# slush_cap_board_rev_e.net
KiCad netlist of a schematic drawn in EAGLE
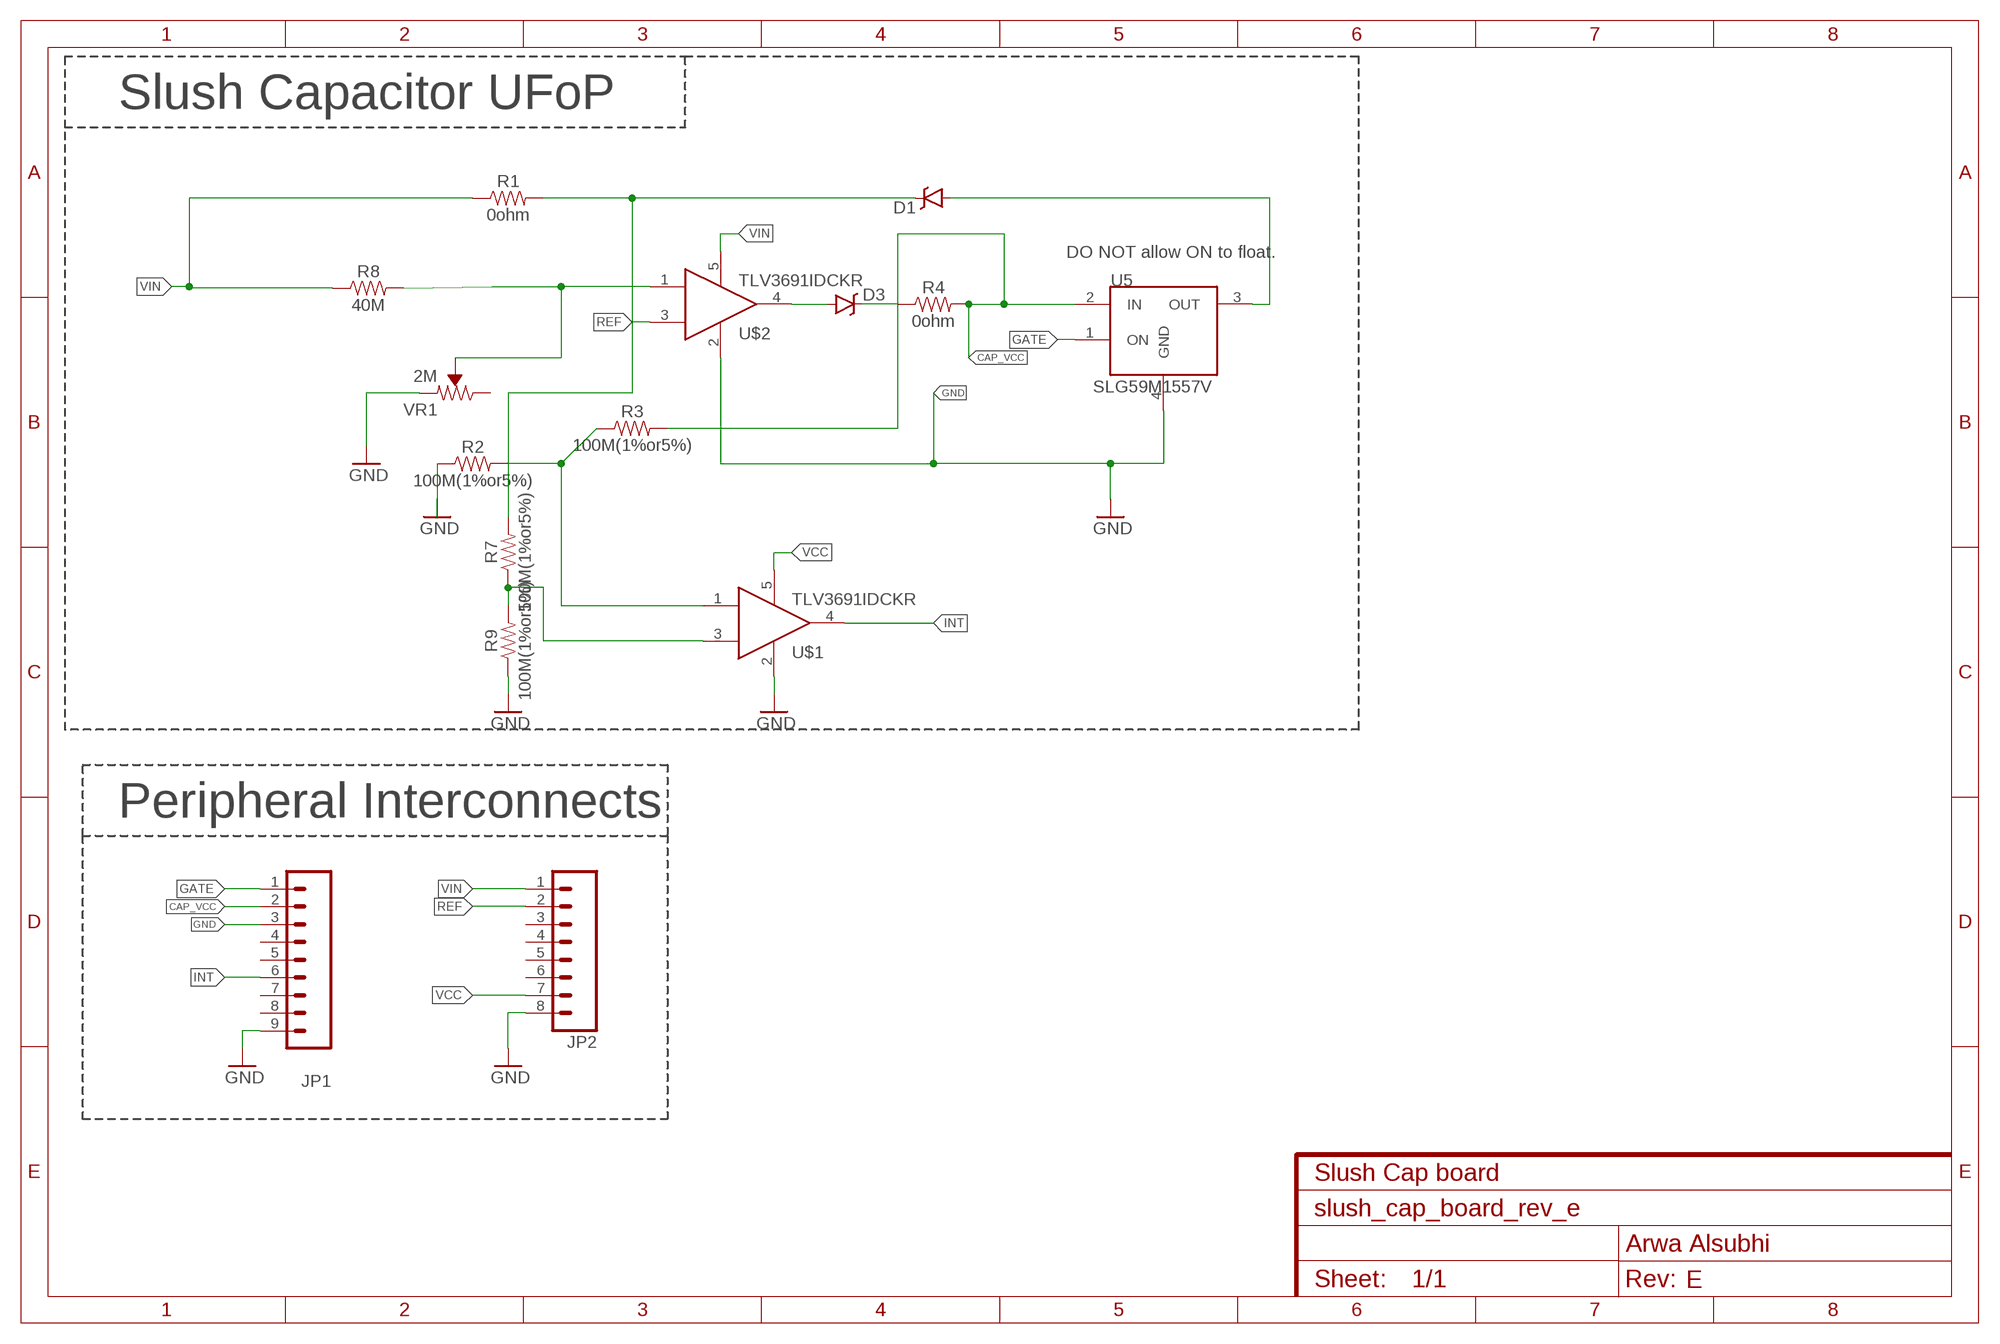
[diagram p0: schematic, sheet 1]

(export (version "E")
  (design (tool "Eeschema 10.0.6"))
  (components
    (comp (ref "D1")
      (value "RB751")
      (footprint "eagle-import:SOD-523")
      (fields (field (name "MPN") "BAS40-02V-V-G-08"))
      (libsource (lib "eagle-import") (part "DIODE-SCHOTTKY-RB751"))
    )
    (comp (ref "D3")
      (value "RB751")
      (footprint "eagle-import:SOD-523")
      (fields (field (name "MPN") "BAS40-02V-V-G-08"))
      (libsource (lib "eagle-import") (part "DIODE-SCHOTTKY-RB751"))
    )
    (comp (ref "JP1")
      (value "M091.27MM")
      (footprint "eagle-import:1X09-1.27MM")
      (fields (field (name "MANUFACTURERPARTNUMBER") "GRPB091VWVN-RC ") (field (name "MPN") "GRPB091VWVN-RC"))
      (libsource (lib "eagle-import") (part "M091.27MM"))
    )
    (comp (ref "JP2")
      (value "M081.27MM")
      (footprint "eagle-import:1X08-1.27MM")
      (fields (field (name "MANUFACTURERPARTNUMBER") "GRPB081VWVN-RC "))
      (libsource (lib "eagle-import") (part "M081.27MM"))
    )
    (comp (ref "R1")
      (value "0ohm")
      (footprint "eagle-import:0603")
      (libsource (lib "eagle-import") (part "0603-RESISTOR-0603-1/10W-1%"))
    )
    (comp (ref "R2")
      (value "100M(1%or5%)")
      (footprint "eagle-import:0805")
      (libsource (lib "eagle-import") (part "0.3OHM-0805-1/8W-1%"))
    )
    (comp (ref "R3")
      (value "100M(1%or5%)")
      (footprint "eagle-import:0805")
      (libsource (lib "eagle-import") (part "0.3OHM-0805-1/8W-1%"))
    )
    (comp (ref "R4")
      (value "0ohm")
      (footprint "eagle-import:0603")
      (libsource (lib "eagle-import") (part "0603-RESISTOR-0603-1/10W-1%"))
    )
    (comp (ref "R7")
      (value "100M(1%or5%)")
      (footprint "eagle-import:0805")
      (libsource (lib "eagle-import") (part "0.3OHM-0805-1/8W-1%"))
    )
    (comp (ref "R8")
      (value "40M")
      (footprint "eagle-import:0805")
      (libsource (lib "eagle-import") (part "0.3OHM-0805-1/8W-1%"))
    )
    (comp (ref "R9")
      (value "100M(1%or5%)")
      (footprint "eagle-import:0805")
      (libsource (lib "eagle-import") (part "0.3OHM-0805-1/8W-1%"))
    )
    (comp (ref "U$1")
      (value "TLV3691IDCKR")
      (footprint "eagle-import:SOT353")
      (libsource (lib "eagle-import") (part "TLV3691IDCKR"))
    )
    (comp (ref "U$2")
      (value "TLV3691IDCKR")
      (footprint "eagle-import:SOT353")
      (libsource (lib "eagle-import") (part "TLV3691IDCKR"))
    )
    (comp (ref "U5")
      (value "SLG59M1557V")
      (footprint "eagle-import:4STDFN")
      (fields (field (name "MPN") "SLG59M1557V "))
      (libsource (lib "eagle-import") (part "SLG59M1557V"))
    )
    (comp (ref "VR1")
      (value "2M")
      (footprint "eagle-import:TRIMPOT-SMD-3MM-CLOSED")
      (libsource (lib "eagle-import") (part "TRIMPOT-SMD-3MM-CLOSED-1/8W-20%"))
    )
  )
  (nets
    (net (code "1") (name "CAP_VCC") (class "Default")
      (node (ref "JP1") (pin "2") (pinfunction "2_2") (pintype "passive"))
      (node (ref "R3") (pin "2") (pinfunction "2_2") (pintype "passive"))
      (node (ref "R4") (pin "2") (pinfunction "2_2") (pintype "passive"))
      (node (ref "U5") (pin "2") (pinfunction "IN_2") (pintype "bidirectional"))
    )
    (net (code "2") (name "GATE") (class "Default")
      (node (ref "JP1") (pin "1") (pinfunction "1_1") (pintype "passive"))
      (node (ref "U5") (pin "1") (pinfunction "ON_1") (pintype "bidirectional"))
    )
    (net (code "3") (name "GND") (class "Default")
      (node (ref "JP1") (pin "3") (pinfunction "3_3") (pintype "passive"))
      (node (ref "JP1") (pin "9") (pinfunction "9_9") (pintype "passive"))
      (node (ref "JP2") (pin "8") (pinfunction "8_8") (pintype "passive"))
      (node (ref "R2") (pin "1") (pinfunction "1_1") (pintype "passive"))
      (node (ref "R9") (pin "1") (pinfunction "1_1") (pintype "passive"))
      (node (ref "U$1") (pin "2") (pinfunction "2_2") (pintype "bidirectional"))
      (node (ref "U$2") (pin "2") (pinfunction "2_2") (pintype "bidirectional"))
      (node (ref "U5") (pin "4") (pinfunction "GND_4") (pintype "bidirectional"))
      (node (ref "VR1") (pin "1") (pinfunction "CCW_1") (pintype "passive"))
    )
    (net (code "4") (name "INT") (class "Default")
      (node (ref "JP1") (pin "6") (pinfunction "6_6") (pintype "passive"))
      (node (ref "U$1") (pin "4") (pinfunction "4_4") (pintype "bidirectional"))
    )
    (net (code "5") (name "Net-(D1-PadC)") (class "Default")
      (node (ref "D1") (pin "C") (pinfunction "C_C") (pintype "passive"))
      (node (ref "R1") (pin "2") (pinfunction "2_2") (pintype "passive"))
      (node (ref "R7") (pin "2") (pinfunction "2_2") (pintype "passive"))
    )
    (net (code "6") (name "Net-(D3-PadA)") (class "Default")
      (node (ref "D3") (pin "A") (pinfunction "A_A") (pintype "passive"))
      (node (ref "U$2") (pin "4") (pinfunction "4_4") (pintype "bidirectional"))
    )
    (net (code "7") (name "Net-(D3-PadC)") (class "Default")
      (node (ref "D3") (pin "C") (pinfunction "C_C") (pintype "passive"))
      (node (ref "R4") (pin "1") (pinfunction "1_1") (pintype "passive"))
    )
    (net (code "8") (name "Net-(R2-Pad2)") (class "Default")
      (node (ref "R2") (pin "2") (pinfunction "2_2") (pintype "passive"))
      (node (ref "R3") (pin "1") (pinfunction "1_1") (pintype "passive"))
      (node (ref "U$1") (pin "1") (pinfunction "1_1") (pintype "bidirectional"))
    )
    (net (code "9") (name "Net-(R7-Pad1)") (class "Default")
      (node (ref "R7") (pin "1") (pinfunction "1_1") (pintype "passive"))
      (node (ref "R9") (pin "2") (pinfunction "2_2") (pintype "passive"))
      (node (ref "U$1") (pin "3") (pinfunction "3_3") (pintype "bidirectional"))
    )
    (net (code "10") (name "Net-(U5-OUT)") (class "Default")
      (node (ref "D1") (pin "A") (pinfunction "A_A") (pintype "passive"))
      (node (ref "U5") (pin "3") (pinfunction "OUT_3") (pintype "bidirectional"))
    )
    (net (code "11") (name "Net-(VR1-WIPER)") (class "Default")
      (node (ref "R8") (pin "2") (pinfunction "2_2") (pintype "passive"))
      (node (ref "U$2") (pin "1") (pinfunction "1_1") (pintype "bidirectional"))
      (node (ref "VR1") (pin "2") (pinfunction "WIPER_2") (pintype "passive"))
    )
    (net (code "12") (name "REF") (class "Default")
      (node (ref "JP2") (pin "2") (pinfunction "2_2") (pintype "passive"))
      (node (ref "U$2") (pin "3") (pinfunction "3_3") (pintype "bidirectional"))
    )
    (net (code "13") (name "VCC") (class "Default")
      (node (ref "JP2") (pin "7") (pinfunction "7_7") (pintype "passive"))
      (node (ref "U$1") (pin "5") (pinfunction "5_5") (pintype "bidirectional"))
    )
    (net (code "14") (name "VIN") (class "Default")
      (node (ref "JP2") (pin "1") (pinfunction "1_1") (pintype "passive"))
      (node (ref "R1") (pin "1") (pinfunction "1_1") (pintype "passive"))
      (node (ref "R8") (pin "1") (pinfunction "1_1") (pintype "passive"))
      (node (ref "U$2") (pin "5") (pinfunction "5_5") (pintype "bidirectional"))
    )
    (net (code "15") (name "unconnected-(JP1-Pad4)") (class "Default")
      (node (ref "JP1") (pin "4") (pinfunction "4_4") (pintype "passive"))
    )
    (net (code "16") (name "unconnected-(JP1-Pad5)") (class "Default")
      (node (ref "JP1") (pin "5") (pinfunction "5_5") (pintype "passive"))
    )
    (net (code "17") (name "unconnected-(JP1-Pad7)") (class "Default")
      (node (ref "JP1") (pin "7") (pinfunction "7_7") (pintype "passive"))
    )
    (net (code "18") (name "unconnected-(JP1-Pad8)") (class "Default")
      (node (ref "JP1") (pin "8") (pinfunction "8_8") (pintype "passive"))
    )
    (net (code "19") (name "unconnected-(JP2-Pad3)") (class "Default")
      (node (ref "JP2") (pin "3") (pinfunction "3_3") (pintype "passive"))
    )
    (net (code "20") (name "unconnected-(JP2-Pad4)") (class "Default")
      (node (ref "JP2") (pin "4") (pinfunction "4_4") (pintype "passive"))
    )
    (net (code "21") (name "unconnected-(JP2-Pad5)") (class "Default")
      (node (ref "JP2") (pin "5") (pinfunction "5_5") (pintype "passive"))
    )
    (net (code "22") (name "unconnected-(JP2-Pad6)") (class "Default")
      (node (ref "JP2") (pin "6") (pinfunction "6_6") (pintype "passive"))
    )
    (net (code "23") (name "unconnected-(VR1-CW-Pad3)") (class "Default")
      (node (ref "VR1") (pin "3") (pinfunction "CW_3") (pintype "passive"))
    )
  )
)
